# 20230531_Sheet1.net
KiCad netlist of a schematic drawn in Altium Designer
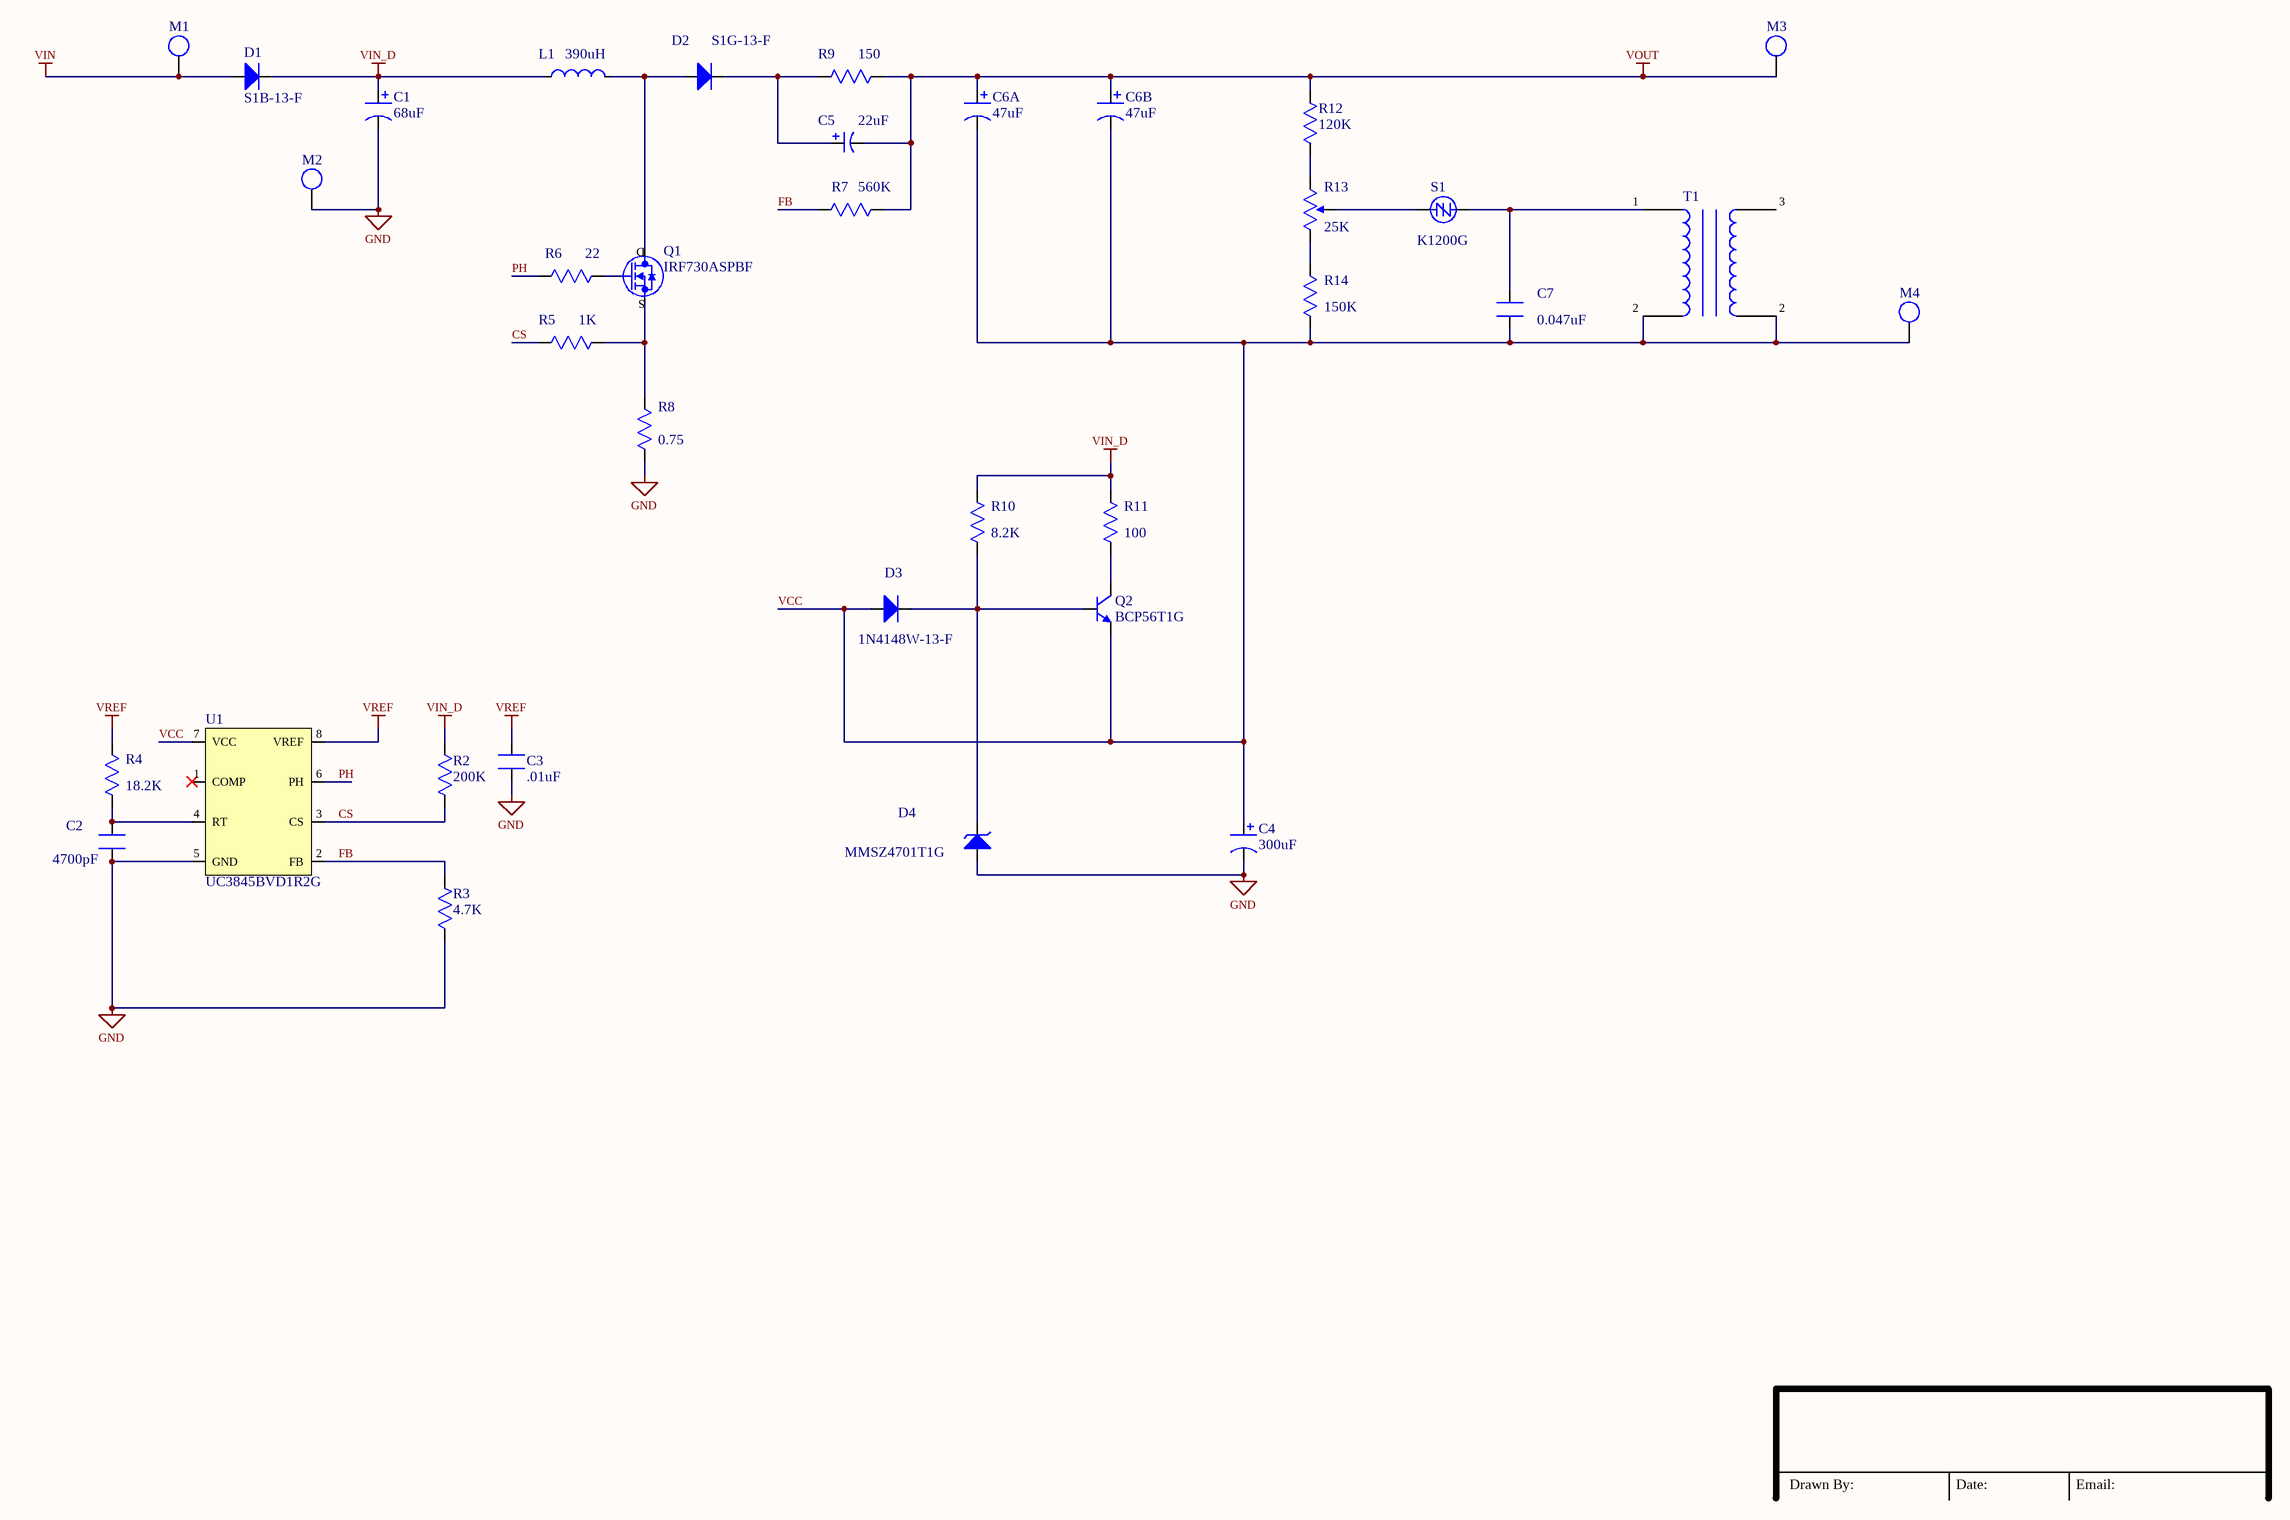
[diagram p0: 20230531_Sheet1.SchDoc]

(export (version "E")
  (design (tool "Eeschema 10.0.6"))
  (components
    (comp (ref "*") (value "TITLE_BLOCK") (libsource (lib "SUPER_LIBRARY") (part "TITLE_BLOCK")))
    (comp (ref "C1")
      (value "68uF")
      (footprint "CAP_POL_13.5_13.5")
      (description "CAP, 68uF, 100V, 20%, AL")
      (fields
        (field (name "MANUFACTURER") "Panasonic Electronic Components")
        (field (name "MPN") "EEE-FK2A680AQ")
      )
      (libsource (lib "SUPER_LIBRARY") (part "COMP-0413"))
    )
    (comp (ref "C2")
      (value "4700pF")
      (footprint "CAP_0603")
      (description "CAP, 4700pF, 50V, 1%, X5R, 0603")
      (fields (field (name "MANUFACTURER") "TDK Corporation") (field (name "MPN") "CGA3E2C0G1H472J080AA"))
      (libsource (lib "SUPER_LIBRARY") (part "COMP-0411"))
    )
    (comp (ref "C3")
      (value ".01uF")
      (footprint "CAP_0603")
      (description "CAP, 0.01uF, 50V, 10%, X7R, 0603")
      (fields
        (field (name "MANUFACTURER") "Samsung Electro-Mechanics")
        (field (name "MPN") "CL10B103KB8NNNL")
      )
      (libsource (lib "SUPER_LIBRARY") (part "COMP-0006"))
    )
    (comp (ref "C4")
      (value "300uF")
      (footprint "CAP_POL_10.3_10.3")
      (description "CAP, 330uF, 35V, RAD 10.3mm x 10.3mm")
      (fields (field (name "MANUFACTURER") "KEMET") (field (name "MPN") "A771MS337M1VLAS014"))
      (libsource (lib "SUPER_LIBRARY") (part "COMP-0335"))
    )
    (comp (ref "C5")
      (value "22uF")
      (footprint "CAP_POL_2917")
      (description "CAP, 22uF, 50V, 20%, TANT")
      (fields (field (name "MANUFACTURER") "KEMET") (field (name "MPN") "T491X226M050AT"))
      (libsource (lib "SUPER_LIBRARY") (part "COMP-0412"))
    )
    (comp (ref "C6A")
      (value "47uF")
      (footprint "CAP_POL_16.3_16.3")
      (description "CAP, 47uF, 250V, 20%, AL")
      (fields (field (name "MANUFACTURER") "KEMET") (field (name "MPN") "EDH476M250A9TAA"))
      (libsource (lib "SUPER_LIBRARY") (part "COMP-0420"))
    )
    (comp (ref "C6B")
      (value "47uF")
      (footprint "CAP_POL_16.3_16.3")
      (description "CAP, 47uF, 250V, 20%, AL")
      (fields (field (name "MANUFACTURER") "KEMET") (field (name "MPN") "EDH476M250A9TAA"))
      (libsource (lib "SUPER_LIBRARY") (part "COMP-0420"))
    )
    (comp (ref "C7")
      (value "0.047uF")
      (footprint "CAP_15MM")
      (description "CAP, 0.047uF, 630V, 15MM")
      (fields (field (name "MANUFACTURER") "KEMET") (field (name "MPN") "R76PI24705050J"))
      (libsource (lib "SUPER_LIBRARY") (part "COMP-0422"))
    )
    (comp (ref "D1")
      (value "S1B-13-F")
      (footprint "DIO_214AC")
      (description "DIO, 100V, 1A")
      (fields (field (name "MANUFACTURER") "Diodes Incorporated"))
      (libsource (lib "SUPER_LIBRARY") (part "COMP-0415"))
    )
    (comp (ref "D2")
      (value "S1G-13-F")
      (footprint "DIO_214AC")
      (description "DIO, 400V, 1A")
      (fields (field (name "MANUFACTURER") "Diodes Incorporated"))
      (libsource (lib "SUPER_LIBRARY") (part "COMP-0416"))
    )
    (comp (ref "D3")
      (value "1N4148W-13-F")
      (footprint "DIO_SOD123")
      (description "DIO, 100V, 300mA")
      (fields (field (name "MANUFACTURER") "Diodes Incorporated"))
      (libsource (lib "SUPER_LIBRARY") (part "COMP-0421"))
    )
    (comp (ref "D4")
      (value "MMSZ4701T1G")
      (footprint "DIO_SOD123")
      (description "DIO, ZENER, 14V")
      (fields (field (name "MANUFACTURER") "onsemi"))
      (libsource (lib "SUPER_LIBRARY") (part "COMP-0417"))
    )
    (comp (ref "L1")
      (value "390uH")
      (footprint "IND_12.5_12.5")
      (description "IND, 390uH, 1A")
      (fields (field (name "MANUFACTURER") "Bourns Inc.") (field (name "MPN") "SRR1280-391K"))
      (libsource (lib "SUPER_LIBRARY") (part "COMP-0419"))
    )
    (comp (ref "M1")
      (value "2MM")
      (footprint "MOUNTING_HOLE_M2")
      (description "Mounting hole, size M2")
      (libsource (lib "SUPER_LIBRARY") (part "MT_M2"))
    )
    (comp (ref "M2")
      (value "2MM")
      (footprint "MOUNTING_HOLE_M2")
      (description "Mounting hole, size M2")
      (libsource (lib "SUPER_LIBRARY") (part "MT_M2"))
    )
    (comp (ref "M3")
      (value "2MM")
      (footprint "MOUNTING_HOLE_M2")
      (description "Mounting hole, size M2")
      (libsource (lib "SUPER_LIBRARY") (part "MT_M2"))
    )
    (comp (ref "M4")
      (value "2MM")
      (footprint "MOUNTING_HOLE_M2")
      (description "Mounting hole, size M2")
      (libsource (lib "SUPER_LIBRARY") (part "MT_M2"))
    )
    (comp (ref "Q1")
      (value "IRF730ASPBF")
      (footprint "FET_TO-263-3")
      (description "TRANS, N-CH,  400V, 5.5A, 74W")
      (fields (field (name "MANUFACTURER") "Vishay Siliconix"))
      (libsource (lib "SUPER_LIBRARY") (part "COMP-0418"))
    )
    (comp (ref "Q2")
      (value "BCP56T1G")
      (footprint "TRANS_SOT-223")
      (description "TRANS, NPN, 80V, 1A")
      (fields (field (name "MANUFACTURER") "onsemi"))
      (libsource (lib "SUPER_LIBRARY") (part "COMP-0414"))
    )
    (comp (ref "R2")
      (value "200K")
      (footprint "RES_1206")
      (description "RES, 200KOHM, 1%, 1/4W, 1206")
      (fields (field (name "MANUFACTURER") "YAGEO") (field (name "MPN") "RC1206FR-07200KL"))
      (libsource (lib "SUPER_LIBRARY") (part "COMP-0407"))
    )
    (comp (ref "R3")
      (value "4.7K")
      (footprint "RES_1206")
      (description "RES, 4.7KOHM, 1%, 1/4W, 1206")
      (fields (field (name "MANUFACTURER") "YAGEO") (field (name "MPN") "RC1206FR-134K7L"))
      (libsource (lib "SUPER_LIBRARY") (part "COMP-0402"))
    )
    (comp (ref "R4")
      (value "18.2K")
      (footprint "RES_1206")
      (description "RES, 18.2KOHM, 1%, 1/4W, 1206")
      (fields (field (name "MANUFACTURER") "YAGEO") (field (name "MPN") "RC1206FR-0718K2L"))
      (libsource (lib "SUPER_LIBRARY") (part "COMP-0405"))
    )
    (comp (ref "R5")
      (value "1K")
      (footprint "RES_1206")
      (description "RES, 1KOHM, 1%, 1/4W, 1206")
      (fields (field (name "MANUFACTURER") "YAGEO") (field (name "MPN") "RC1206FR-071KL"))
      (libsource (lib "SUPER_LIBRARY") (part "COMP-0400"))
    )
    (comp (ref "R6")
      (value "22")
      (footprint "RES_1206")
      (description "RES, 22OHM, 1%, 1/4W, 1206")
      (fields (field (name "MANUFACTURER") "YAGEO") (field (name "MPN") "RC1206FR-1022RL"))
      (libsource (lib "SUPER_LIBRARY") (part "COMP-0403"))
    )
    (comp (ref "R7")
      (value "560K")
      (footprint "RES_1206")
      (description "RES, 560KOHM, 1%, 1/4W, 1206")
      (fields (field (name "MANUFACTURER") "YAGEO") (field (name "MPN") "RC1206FR-07560KL"))
      (libsource (lib "SUPER_LIBRARY") (part "COMP-0404"))
    )
    (comp (ref "R8")
      (value "0.75")
      (footprint "RES_1206")
      (description "RES, 0.75OHM, 1%, 1W, 1206")
      (fields (field (name "MANUFACTURER") "YAGEO") (field (name "MPN") "PE1206FRF470R75L"))
      (libsource (lib "SUPER_LIBRARY") (part "COMP-0410"))
    )
    (comp (ref "R9")
      (value "150")
      (footprint "RES_1206")
      (description "RES, 150OHM, 1%, 1/2W, 1206")
      (fields (field (name "MANUFACTURER") "Vishay Dale") (field (name "MPN") "CRCW1210150RFKEA"))
      (libsource (lib "SUPER_LIBRARY") (part "COMP-0409"))
    )
    (comp (ref "R10")
      (value "8.2K")
      (footprint "RES_1206")
      (description "RES, 8.2KOHM, 1%, 1/4W, 1206")
      (fields (field (name "MANUFACTURER") "YAGEO") (field (name "MPN") "RC1206FR-078K2L"))
      (libsource (lib "SUPER_LIBRARY") (part "COMP-0408"))
    )
    (comp (ref "R11")
      (value "100")
      (footprint "RES_1206")
      (description "RES, 100OHM, 1/4W, 1%, 1206")
      (fields (field (name "MANUFACTURER") "YAGEO") (field (name "MPN") "RC1206FR-13100RL"))
      (libsource (lib "SUPER_LIBRARY") (part "COMP-0399"))
    )
    (comp (ref "R12")
      (value "120K")
      (footprint "RES_1206")
      (description "RES, 120KOHM, 1%, 1/4W, 1206")
      (fields (field (name "MANUFACTURER") "YAGEO") (field (name "MPN") "RC1206FR-07120KL"))
      (libsource (lib "SUPER_LIBRARY") (part "COMP-0401"))
    )
    (comp (ref "R13")
      (value "25K")
      (footprint "POT_")
      (description "POT, 25KOHM")
      (fields (field (name "MANUFACTURER") "Bourns Inc.") (field (name "MPN") "3361P-1-253GLF"))
      (libsource (lib "SUPER_LIBRARY") (part "COMP-0434"))
    )
    (comp (ref "R14")
      (value "150K")
      (footprint "RES_1206")
      (description "RES, 150KOHM, 1%, 1/4W, 1206")
      (fields (field (name "MANUFACTURER") "YAGEO") (field (name "MPN") "RC1206FR-07150KL"))
      (libsource (lib "SUPER_LIBRARY") (part "COMP-0406"))
    )
    (comp (ref "S1")
      (value "K1200G")
      (footprint "SIDAC_TH1")
      (description "SIDAC, 125V, 150mA")
      (libsource (lib "SUPER_LIBRARY") (part "COMP-0435"))
    )
    (comp (ref "T1")
      (value "COMP-0433")
      (footprint "XFMR_Custom2")
      (description "XFMR, TRIGGER")
      (libsource (lib "SUPER_LIBRARY") (part "COMP-0433"))
    )
    (comp (ref "U1")
      (value "UC3845BVD1R2G")
      (footprint "IC_8_SOIC")
      (description "IC, POWER MGMT, BOOST REGULATOR, 30V, 105C, SOIC-8")
      (fields (field (name "MANUFACTURER") "onsemi"))
      (libsource (lib "SUPER_LIBRARY") (part "COMP-0398"))
    )
  )
  (nets
    (net (code "1") (name "/CS") (class "Default")
      (node (ref "R2") (pin "1") (pinfunction "1_1") (pintype "passive"))
      (node (ref "R5") (pin "1") (pinfunction "1_1") (pintype "passive"))
      (node (ref "U1") (pin "3") (pinfunction "CS_3") (pintype "passive"))
    )
    (net (code "2") (name "/FB") (class "Default")
      (node (ref "R3") (pin "2") (pinfunction "2_2") (pintype "passive"))
      (node (ref "R7") (pin "1") (pinfunction "1_1") (pintype "passive"))
      (node (ref "U1") (pin "2") (pinfunction "FB_2") (pintype "passive"))
    )
    (net (code "3") (name "/PH") (class "Default")
      (node (ref "R6") (pin "1") (pinfunction "1_1") (pintype "passive"))
      (node (ref "U1") (pin "6") (pinfunction "PH_6") (pintype "passive"))
    )
    (net (code "4") (name "/VCC") (class "Default")
      (node (ref "C4") (pin "1") (pinfunction "1_1") (pintype "passive"))
      (node (ref "C6A") (pin "2") (pinfunction "2_2") (pintype "passive"))
      (node (ref "C6B") (pin "2") (pinfunction "2_2") (pintype "passive"))
      (node (ref "C7") (pin "2") (pinfunction "2_2") (pintype "passive"))
      (node (ref "D3") (pin "2") (pinfunction "A_2") (pintype "passive"))
      (node (ref "M4") (pin "1") (pinfunction "1_1") (pintype "passive"))
      (node (ref "Q2") (pin "2") (pinfunction "E_2") (pintype "passive"))
      (node (ref "R14") (pin "1") (pinfunction "1_1") (pintype "passive"))
      (node (ref "T1") (pin "2") (pinfunction "2_2") (pintype "passive"))
      (node (ref "U1") (pin "7") (pinfunction "VCC_7") (pintype "passive"))
    )
    (net (code "5") (name "GND") (class "Default")
      (node (ref "C1") (pin "2") (pinfunction "2_2") (pintype "passive"))
      (node (ref "C2") (pin "2") (pinfunction "2_2") (pintype "passive"))
      (node (ref "C3") (pin "2") (pinfunction "2_2") (pintype "passive"))
      (node (ref "C4") (pin "2") (pinfunction "2_2") (pintype "passive"))
      (node (ref "D4") (pin "2") (pinfunction "A_2") (pintype "passive"))
      (node (ref "M2") (pin "1") (pinfunction "1_1") (pintype "passive"))
      (node (ref "R3") (pin "1") (pinfunction "1_1") (pintype "passive"))
      (node (ref "R8") (pin "1") (pinfunction "1_1") (pintype "passive"))
      (node (ref "U1") (pin "5") (pinfunction "GND_5") (pintype "passive"))
    )
    (net (code "6") (name "Net-(C7-Pad1)") (class "Default")
      (node (ref "C7") (pin "1") (pinfunction "1_1") (pintype "passive"))
      (node (ref "S1") (pin "2") (pinfunction "2_2") (pintype "passive"))
      (node (ref "T1") (pin "1") (pinfunction "1_1") (pintype "passive"))
    )
    (net (code "7") (name "Net-(D2-A)") (class "Default")
      (node (ref "D2") (pin "2") (pinfunction "A_2") (pintype "passive"))
      (node (ref "L1") (pin "2") (pinfunction "2_2") (pintype "passive"))
      (node (ref "Q1") (pin "2") (pinfunction "D_2") (pintype "passive"))
    )
    (net (code "8") (name "Net-(D2-K)") (class "Default")
      (node (ref "C5") (pin "1") (pinfunction "1_1") (pintype "passive"))
      (node (ref "D2") (pin "1") (pinfunction "K_1") (pintype "passive"))
      (node (ref "R9") (pin "1") (pinfunction "1_1") (pintype "passive"))
    )
    (net (code "9") (name "Net-(D3-K)") (class "Default")
      (node (ref "D3") (pin "1") (pinfunction "K_1") (pintype "passive"))
      (node (ref "D4") (pin "1") (pinfunction "A_1") (pintype "passive"))
      (node (ref "Q2") (pin "1") (pinfunction "B_1") (pintype "passive"))
      (node (ref "R10") (pin "1") (pinfunction "1_1") (pintype "passive"))
    )
    (net (code "10") (name "Net-(Q1-G)") (class "Default")
      (node (ref "Q1") (pin "1") (pinfunction "G_1") (pintype "passive"))
      (node (ref "R6") (pin "2") (pinfunction "2_2") (pintype "passive"))
    )
    (net (code "11") (name "Net-(Q1-S)") (class "Default")
      (node (ref "Q1") (pin "3") (pinfunction "S_3") (pintype "passive"))
      (node (ref "R5") (pin "2") (pinfunction "2_2") (pintype "passive"))
      (node (ref "R8") (pin "2") (pinfunction "2_2") (pintype "passive"))
    )
    (net (code "12") (name "Net-(Q2-C)") (class "Default")
      (node (ref "Q2") (pin "3") (pinfunction "C_3") (pintype "passive"))
      (node (ref "R11") (pin "1") (pinfunction "1_1") (pintype "passive"))
    )
    (net (code "13") (name "Net-(R12-Pad1)") (class "Default")
      (node (ref "R12") (pin "1") (pinfunction "1_1") (pintype "passive"))
      (node (ref "R13") (pin "1") (pinfunction "1_1") (pintype "passive"))
    )
    (net (code "14") (name "Net-(R13-Pad2)") (class "Default")
      (node (ref "R13") (pin "2") (pinfunction "2_2") (pintype "passive"))
      (node (ref "S1") (pin "1") (pinfunction "1_1") (pintype "passive"))
    )
    (net (code "15") (name "Net-(R13-Pad3)") (class "Default")
      (node (ref "R13") (pin "3") (pinfunction "3_3") (pintype "passive"))
      (node (ref "R14") (pin "2") (pinfunction "2_2") (pintype "passive"))
    )
    (net (code "16") (name "Net-(U1-RT)") (class "Default")
      (node (ref "C2") (pin "1") (pinfunction "1_1") (pintype "passive"))
      (node (ref "R4") (pin "1") (pinfunction "1_1") (pintype "passive"))
      (node (ref "U1") (pin "4") (pinfunction "RT_4") (pintype "passive"))
    )
    (net (code "17") (name "VIN") (class "Default")
      (node (ref "D1") (pin "2") (pinfunction "A_2") (pintype "passive"))
      (node (ref "M1") (pin "1") (pinfunction "1_1") (pintype "passive"))
    )
    (net (code "18") (name "VIN_D") (class "Default")
      (node (ref "C1") (pin "1") (pinfunction "1_1") (pintype "passive"))
      (node (ref "D1") (pin "1") (pinfunction "K_1") (pintype "passive"))
      (node (ref "L1") (pin "1") (pinfunction "1_1") (pintype "passive"))
      (node (ref "R10") (pin "2") (pinfunction "2_2") (pintype "passive"))
      (node (ref "R11") (pin "2") (pinfunction "2_2") (pintype "passive"))
      (node (ref "R2") (pin "2") (pinfunction "2_2") (pintype "passive"))
    )
    (net (code "19") (name "VOUT") (class "Default")
      (node (ref "C5") (pin "2") (pinfunction "2_2") (pintype "passive"))
      (node (ref "C6A") (pin "1") (pinfunction "1_1") (pintype "passive"))
      (node (ref "C6B") (pin "1") (pinfunction "1_1") (pintype "passive"))
      (node (ref "M3") (pin "1") (pinfunction "1_1") (pintype "passive"))
      (node (ref "R12") (pin "2") (pinfunction "2_2") (pintype "passive"))
      (node (ref "R7") (pin "2") (pinfunction "2_2") (pintype "passive"))
      (node (ref "R9") (pin "2") (pinfunction "2_2") (pintype "passive"))
    )
    (net (code "20") (name "VREF") (class "Default")
      (node (ref "C3") (pin "1") (pinfunction "1_1") (pintype "passive"))
      (node (ref "R4") (pin "2") (pinfunction "2_2") (pintype "passive"))
      (node (ref "U1") (pin "8") (pinfunction "VREF_8") (pintype "passive"))
    )
    (net (code "21") (name "unconnected-(T1-Pad3)") (class "Default")
      (node (ref "T1") (pin "3") (pinfunction "3_3") (pintype "passive"))
    )
    (net (code "22") (name "unconnected-(U1-COMP-Pad1)") (class "Default")
      (node (ref "U1") (pin "1") (pinfunction "COMP_1") (pintype "passive+no_connect"))
    )
  )
)
